# ProPrj_51__2025-03-03.net
KiCad netlist of a schematic drawn in EasyEDA Pro
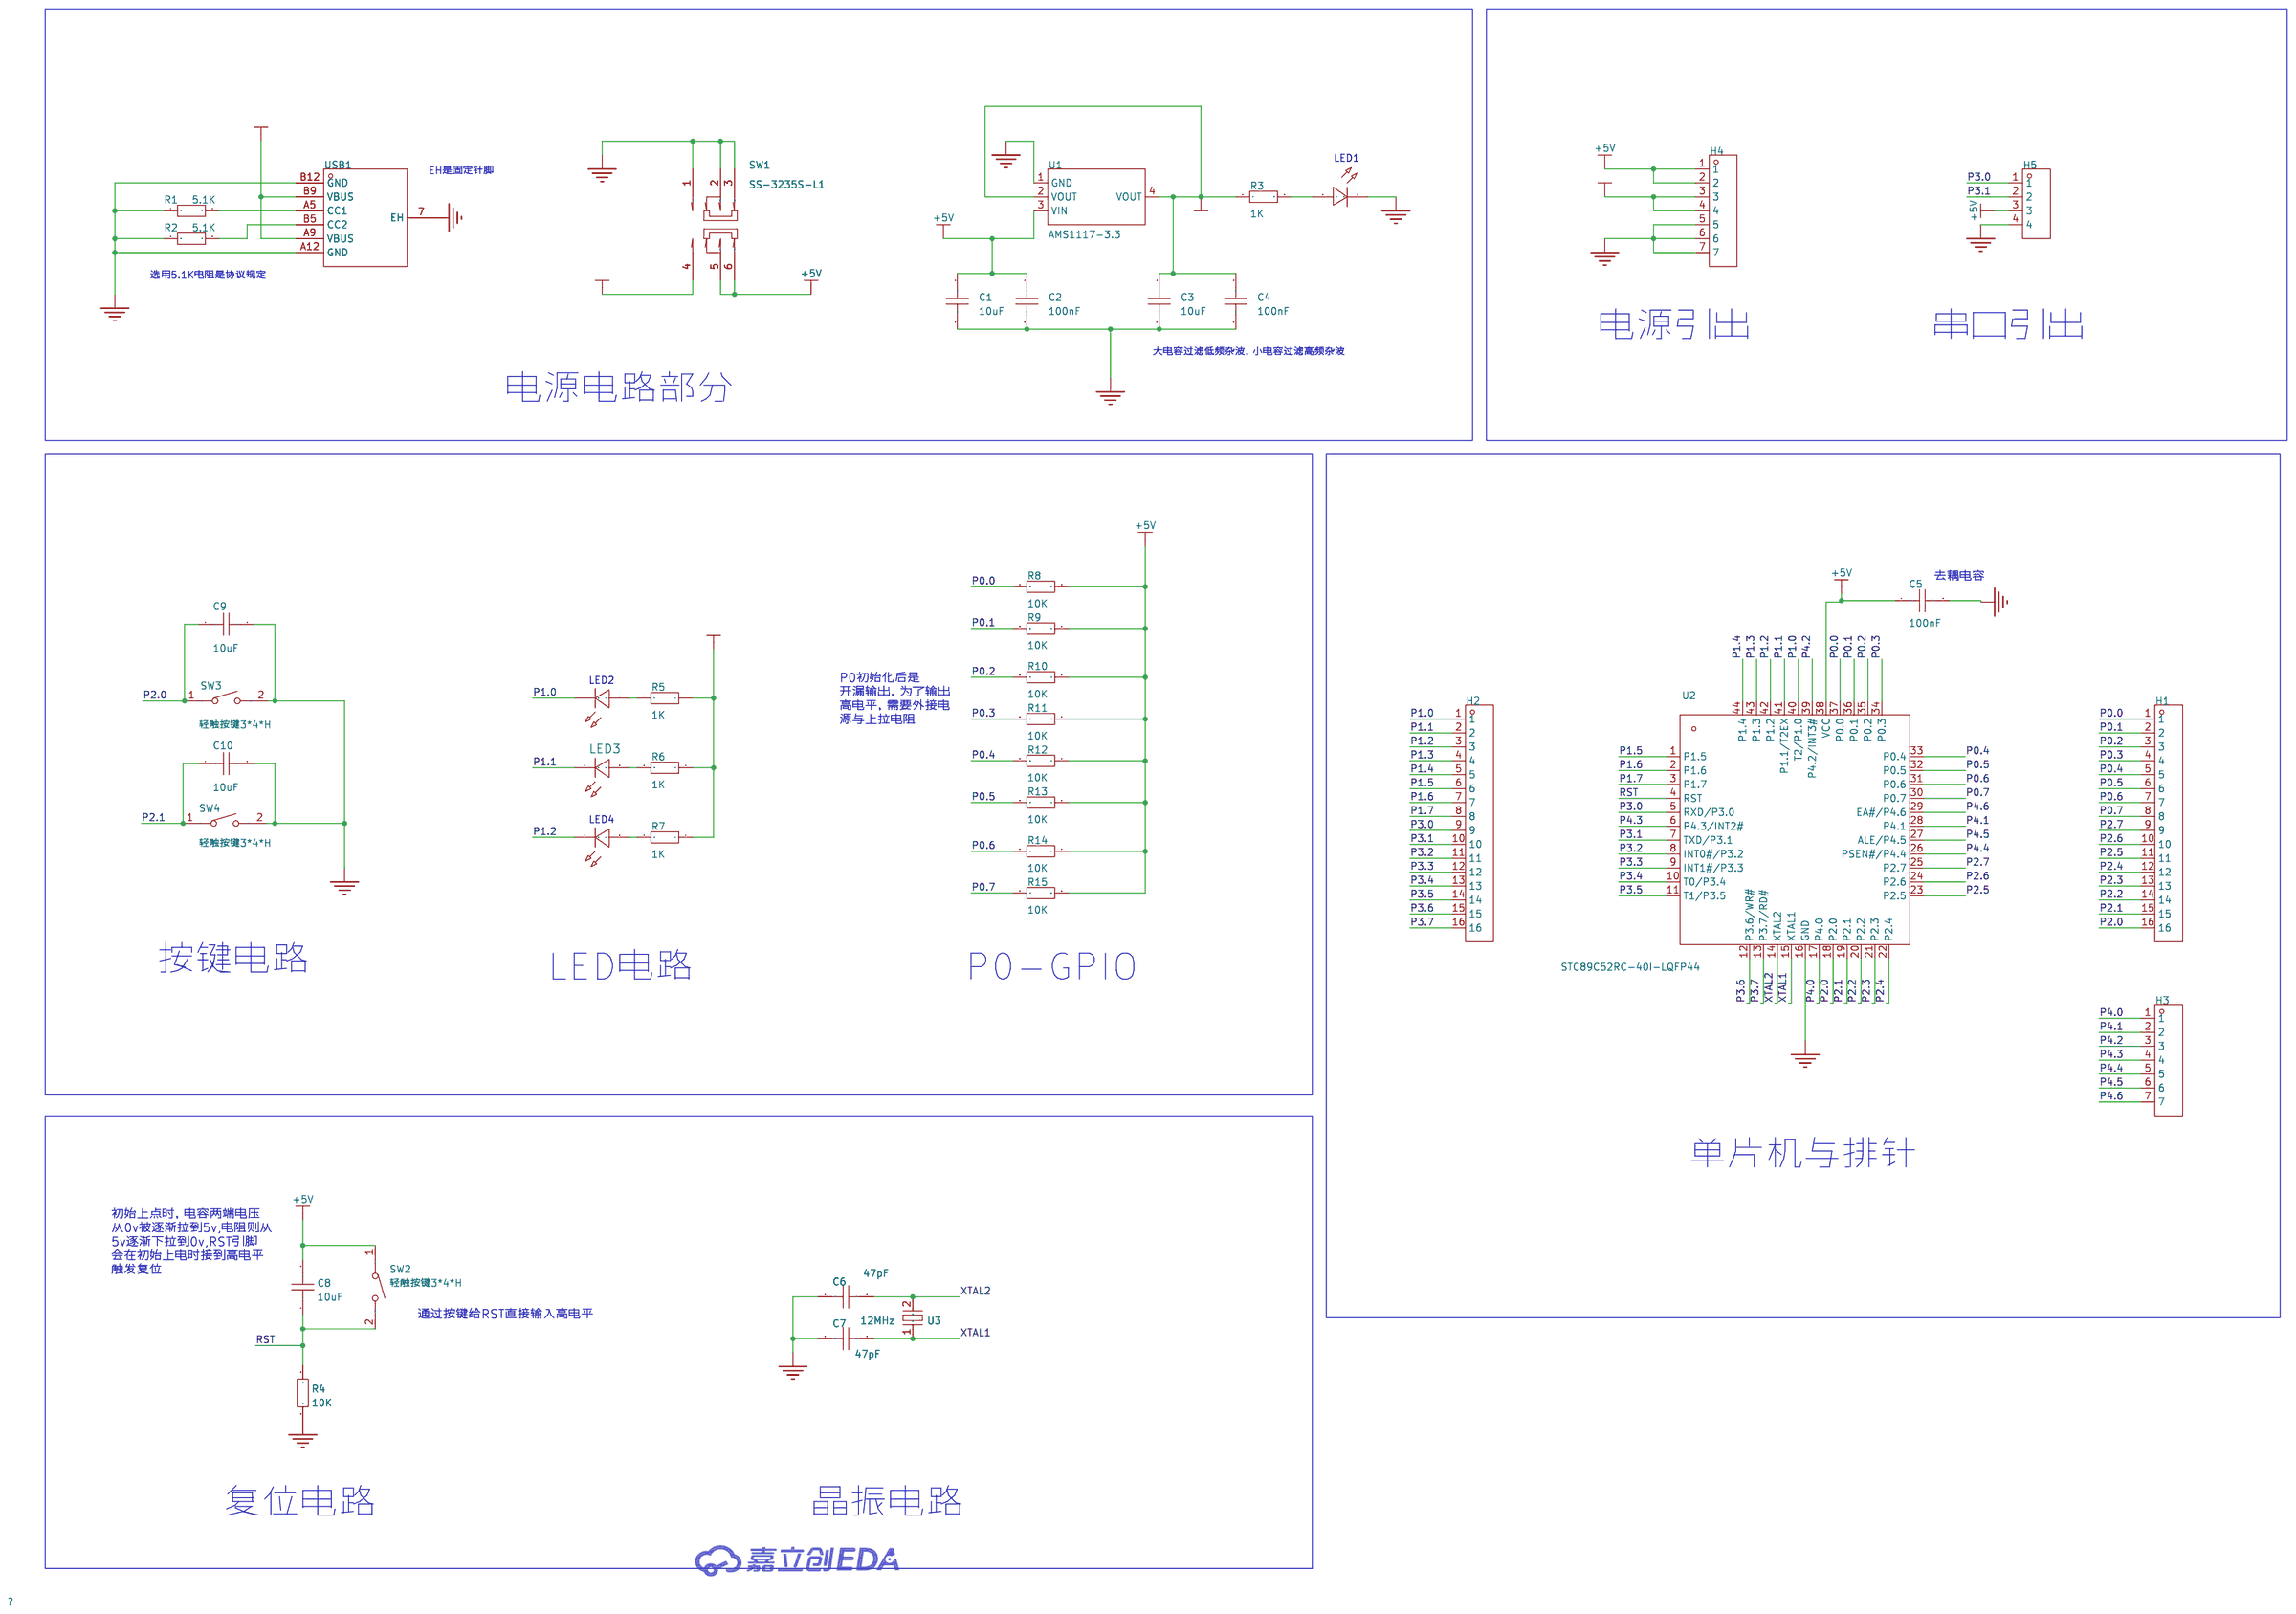
[diagram p0: schematic sheet]

(export (version "E")
  (design (tool "Eeschema 10.0.6"))
  (components
    (comp (ref "C1")
      (value "10uF")
      (footprint "easyedapro:C0805")
      (libsource (lib "easyedapro") (part "CapAcitance"))
    )
    (comp (ref "C2")
      (value "100nF")
      (footprint "easyedapro:C0805")
      (libsource (lib "easyedapro") (part "CapAcitance"))
    )
    (comp (ref "C3")
      (value "10uF")
      (footprint "easyedapro:C0805")
      (libsource (lib "easyedapro") (part "CapAcitance"))
    )
    (comp (ref "C4")
      (value "100nF")
      (footprint "easyedapro:C0805")
      (libsource (lib "easyedapro") (part "CapAcitance"))
    )
    (comp (ref "C5")
      (value "100nF")
      (footprint "easyedapro:C0805")
      (libsource (lib "easyedapro") (part "CapAcitance"))
    )
    (comp (ref "C6")
      (value "47pF")
      (footprint "easyedapro:C0805")
      (libsource (lib "easyedapro") (part "CapAcitance"))
    )
    (comp (ref "C7")
      (value "47pF")
      (footprint "easyedapro:C0805")
      (libsource (lib "easyedapro") (part "CapAcitance"))
    )
    (comp (ref "C8")
      (value "10uF")
      (footprint "easyedapro:C0805")
      (libsource (lib "easyedapro") (part "CapAcitance"))
    )
    (comp (ref "C9")
      (value "10uF")
      (footprint "easyedapro:C0805")
      (libsource (lib "easyedapro") (part "CapAcitance"))
    )
    (comp (ref "C10")
      (value "10uF")
      (footprint "easyedapro:C0805")
      (libsource (lib "easyedapro") (part "CapAcitance"))
    )
    (comp (ref "H1")
      (value "~")
      (footprint "easyedapro:HDR-TH_16P-P2.54-V-M")
      (libsource (lib "easyedapro") (part "HDR_2.54-1x16P"))
    )
    (comp (ref "H2")
      (value "~")
      (footprint "easyedapro:HDR-TH_16P-P2.54-V-M")
      (libsource (lib "easyedapro") (part "HDR_2.54-1x16P"))
    )
    (comp (ref "H3")
      (value "~")
      (footprint "easyedapro:HDR-TH_7P-P2.54-V-M")
      (libsource (lib "easyedapro") (part "PZ254V-11-07P"))
    )
    (comp (ref "H4")
      (value "~")
      (footprint "easyedapro:HDR-TH_7P-P2.54-V-M")
      (libsource (lib "easyedapro") (part "PZ254V-11-07P"))
    )
    (comp (ref "H5")
      (value "~")
      (footprint "easyedapro:HDR-TH_4P-P2.54-V-M")
      (libsource (lib "easyedapro") (part "PZ254V-11-04P"))
    )
    (comp (ref "LED1")
      (value "~")
      (footprint "easyedapro:LED_0805")
      (libsource (lib "easyedapro") (part "LED_G"))
    )
    (comp (ref "LED2")
      (value "~")
      (footprint "easyedapro:LED_0805")
      (libsource (lib "easyedapro") (part "LED_G"))
    )
    (comp (ref "LED3")
      (value "~")
      (footprint "easyedapro:LED_0805")
      (libsource (lib "easyedapro") (part "LED_R"))
    )
    (comp (ref "LED4")
      (value "~")
      (footprint "easyedapro:LED_0805")
      (libsource (lib "easyedapro") (part "LED_B"))
    )
    (comp (ref "R1") (value "5.1K") (footprint "easyedapro:R0805") (libsource (lib "easyedapro") (part "电阻")))
    (comp (ref "R2") (value "5.1K") (footprint "easyedapro:R0805") (libsource (lib "easyedapro") (part "电阻")))
    (comp (ref "R3") (value "1K") (footprint "easyedapro:R0805") (libsource (lib "easyedapro") (part "电阻")))
    (comp (ref "R4") (value "10K") (footprint "easyedapro:R0805") (libsource (lib "easyedapro") (part "电阻")))
    (comp (ref "R5") (value "1K") (footprint "easyedapro:R0805") (libsource (lib "easyedapro") (part "电阻")))
    (comp (ref "R6") (value "1K") (footprint "easyedapro:R0805") (libsource (lib "easyedapro") (part "电阻")))
    (comp (ref "R7") (value "1K") (footprint "easyedapro:R0805") (libsource (lib "easyedapro") (part "电阻")))
    (comp (ref "R8") (value "10K") (footprint "easyedapro:R0805") (libsource (lib "easyedapro") (part "电阻")))
    (comp (ref "R9") (value "10K") (footprint "easyedapro:R0805") (libsource (lib "easyedapro") (part "电阻")))
    (comp (ref "R10") (value "10K") (footprint "easyedapro:R0805") (libsource (lib "easyedapro") (part "电阻")))
    (comp (ref "R11") (value "10K") (footprint "easyedapro:R0805") (libsource (lib "easyedapro") (part "电阻")))
    (comp (ref "R12") (value "10K") (footprint "easyedapro:R0805") (libsource (lib "easyedapro") (part "电阻")))
    (comp (ref "R13") (value "10K") (footprint "easyedapro:R0805") (libsource (lib "easyedapro") (part "电阻")))
    (comp (ref "R14") (value "10K") (footprint "easyedapro:R0805") (libsource (lib "easyedapro") (part "电阻")))
    (comp (ref "R15") (value "10K") (footprint "easyedapro:R0805") (libsource (lib "easyedapro") (part "电阻")))
    (comp (ref "SW1")
      (value "SS-3235S-L1")
      (footprint "easyedapro:SW-SMD_SS-3235S-LX")
      (description "电路结构:双刀双掷;安装方式:卧贴;开关颜色:黑色;额定电流(DC):50mA;额定电压(DC):12V;额定电流(AC):50mA;额定电压(AC):12V;机械寿命:1万次;")
      (fields (field (name "Manufacturer") "XKB Connectivity(中国星坤)"))
      (libsource (lib "easyedapro") (part "SS-3235S-L1"))
    )
    (comp (ref "SW2")
      (value "轻触按键3*4*H")
      (footprint "easyedapro:SW-SMD_L4.0-W2.9-LS5.0")
      (libsource (lib "easyedapro") (part "轻触按键3*4*H"))
    )
    (comp (ref "SW3")
      (value "轻触按键3*4*H")
      (footprint "easyedapro:SW-SMD_L4.0-W2.9-LS5.0")
      (libsource (lib "easyedapro") (part "轻触按键3*4*H"))
    )
    (comp (ref "SW4")
      (value "轻触按键3*4*H")
      (footprint "easyedapro:SW-SMD_L4.0-W2.9-LS5.0")
      (libsource (lib "easyedapro") (part "轻触按键3*4*H"))
    )
    (comp (ref "U1")
      (value "AMS1117-3.3")
      (footprint "easyedapro:SOT-223-3_L6.5-W3.4-P2.30-LS7.0-BR")
      (description "输出类型:固定;工作电压:-;输出电压:3.3V;输出电流:1A;电源纹波抑制比(PSRR):72dB@(120Hz);输出极性:正极;")
      (fields (field (name "Manufacturer") "AMS"))
      (libsource (lib "easyedapro") (part "AMS1117-3.3"))
    )
    (comp (ref "U2")
      (value "STC89C52RC-40I-LQFP44")
      (footprint "easyedapro:LQFP-44_L10.0-W10.0-P0.80-LS12.0-BL")
      (description "CPU内核:51系列;应用领域:-;")
      (fields (field (name "Manufacturer") "STC"))
      (libsource (lib "easyedapro") (part "STC89C52RC-40I_C8707"))
    )
    (comp (ref "U3")
      (value "12MHz")
      (footprint "easyedapro:CRYSTAL-SMD_L11.4-W4.7-LS12.7")
      (description "频率:12MHz;常温频差:±30ppm;外接负载电容:18pF;频率稳定度(全温):±35ppm;")
      (fields
        (field (name "Manufacturer Part") "ABLS-12.000MHZ-B4H-T")
        (field (name "Manufacturer") "ABRACON")
      )
      (libsource (lib "easyedapro") (part "ABLS-12.000MHZ-B4H-T"))
    )
    (comp (ref "USB1")
      (value "TYPE-C-6P-DIP2X2")
      (footprint "easyedapro:TYPE-C-SMD_TYPE-C-6P")
      (libsource (lib "easyedapro") (part "TYPE-C-6P-DIP2X2"))
    )
  )
  (nets
    (net (code "1") (name "+3.3V") (class "Default")
      (node (ref "C3") (pin "1") (pinfunction "1_1") (pintype "input"))
      (node (ref "C4") (pin "1") (pinfunction "1_1") (pintype "input"))
      (node (ref "H4") (pin "3") (pinfunction "3_3") (pintype "unspecified"))
      (node (ref "H4") (pin "4") (pinfunction "4_4") (pintype "unspecified"))
      (node (ref "R3") (pin "1") (pinfunction "1_1") (pintype "input"))
      (node (ref "R5") (pin "1") (pinfunction "1_1") (pintype "input"))
      (node (ref "R6") (pin "1") (pinfunction "1_1") (pintype "input"))
      (node (ref "R7") (pin "1") (pinfunction "1_1") (pintype "input"))
      (node (ref "U1") (pin "2") (pinfunction "VOUT_2") (pintype "unspecified"))
      (node (ref "U1") (pin "4") (pinfunction "VOUT_4") (pintype "unspecified"))
    )
    (net (code "2") (name "+5V") (class "Default")
      (node (ref "C1") (pin "1") (pinfunction "1_1") (pintype "input"))
      (node (ref "C2") (pin "1") (pinfunction "1_1") (pintype "input"))
      (node (ref "C5") (pin "1") (pinfunction "1_1") (pintype "input"))
      (node (ref "C8") (pin "2") (pinfunction "2_2") (pintype "input"))
      (node (ref "H4") (pin "1") (pinfunction "1_1") (pintype "unspecified"))
      (node (ref "H4") (pin "2") (pinfunction "2_2") (pintype "unspecified"))
      (node (ref "H5") (pin "3") (pinfunction "3_3") (pintype "unspecified"))
      (node (ref "R10") (pin "1") (pinfunction "1_1") (pintype "input"))
      (node (ref "R11") (pin "1") (pinfunction "1_1") (pintype "input"))
      (node (ref "R12") (pin "1") (pinfunction "1_1") (pintype "input"))
      (node (ref "R13") (pin "1") (pinfunction "1_1") (pintype "input"))
      (node (ref "R14") (pin "1") (pinfunction "1_1") (pintype "input"))
      (node (ref "R15") (pin "1") (pinfunction "1_1") (pintype "input"))
      (node (ref "R8") (pin "1") (pinfunction "1_1") (pintype "input"))
      (node (ref "R9") (pin "1") (pinfunction "1_1") (pintype "input"))
      (node (ref "SW1") (pin "5") (pinfunction "5_5") (pintype "unspecified"))
      (node (ref "SW1") (pin "6") (pinfunction "6_6") (pintype "unspecified"))
      (node (ref "SW2") (pin "1") (pinfunction "1_1") (pintype "unspecified"))
      (node (ref "U1") (pin "3") (pinfunction "VIN_3") (pintype "unspecified"))
      (node (ref "U2") (pin "38") (pinfunction "VCC_38") (pintype "unspecified"))
    )
    (net (code "3") (name "/P0.0") (class "Default")
      (node (ref "H1") (pin "1") (pinfunction "1_1") (pintype "input"))
      (node (ref "R8") (pin "2") (pinfunction "2_2") (pintype "input"))
      (node (ref "U2") (pin "37") (pinfunction "P0.0_37") (pintype "unspecified"))
    )
    (net (code "4") (name "/P0.1") (class "Default")
      (node (ref "H1") (pin "2") (pinfunction "2_2") (pintype "input"))
      (node (ref "R9") (pin "2") (pinfunction "2_2") (pintype "input"))
      (node (ref "U2") (pin "36") (pinfunction "P0.1_36") (pintype "unspecified"))
    )
    (net (code "5") (name "/P0.2") (class "Default")
      (node (ref "H1") (pin "3") (pinfunction "3_3") (pintype "input"))
      (node (ref "R10") (pin "2") (pinfunction "2_2") (pintype "input"))
      (node (ref "U2") (pin "35") (pinfunction "P0.2_35") (pintype "unspecified"))
    )
    (net (code "6") (name "/P0.3") (class "Default")
      (node (ref "H1") (pin "4") (pinfunction "4_4") (pintype "input"))
      (node (ref "R11") (pin "2") (pinfunction "2_2") (pintype "input"))
      (node (ref "U2") (pin "34") (pinfunction "P0.3_34") (pintype "unspecified"))
    )
    (net (code "7") (name "/P0.4") (class "Default")
      (node (ref "H1") (pin "5") (pinfunction "5_5") (pintype "input"))
      (node (ref "R12") (pin "2") (pinfunction "2_2") (pintype "input"))
      (node (ref "U2") (pin "33") (pinfunction "P0.4_33") (pintype "unspecified"))
    )
    (net (code "8") (name "/P0.5") (class "Default")
      (node (ref "H1") (pin "6") (pinfunction "6_6") (pintype "input"))
      (node (ref "R13") (pin "2") (pinfunction "2_2") (pintype "input"))
      (node (ref "U2") (pin "32") (pinfunction "P0.5_32") (pintype "unspecified"))
    )
    (net (code "9") (name "/P0.6") (class "Default")
      (node (ref "H1") (pin "7") (pinfunction "7_7") (pintype "input"))
      (node (ref "R14") (pin "2") (pinfunction "2_2") (pintype "input"))
      (node (ref "U2") (pin "31") (pinfunction "P0.6_31") (pintype "unspecified"))
    )
    (net (code "10") (name "/P0.7") (class "Default")
      (node (ref "H1") (pin "8") (pinfunction "8_8") (pintype "input"))
      (node (ref "R15") (pin "2") (pinfunction "2_2") (pintype "input"))
      (node (ref "U2") (pin "30") (pinfunction "P0.7_30") (pintype "unspecified"))
    )
    (net (code "11") (name "/P1.0") (class "Default")
      (node (ref "H2") (pin "1") (pinfunction "1_1") (pintype "input"))
      (node (ref "LED2") (pin "1") (pinfunction "C_1") (pintype "input"))
      (node (ref "U2") (pin "40") (pinfunction "T2/P1.0_40") (pintype "unspecified"))
    )
    (net (code "12") (name "/P1.1") (class "Default")
      (node (ref "H2") (pin "2") (pinfunction "2_2") (pintype "input"))
      (node (ref "LED3") (pin "1") (pinfunction "C_1") (pintype "input"))
      (node (ref "U2") (pin "41") (pinfunction "P1.1/T2EX_41") (pintype "unspecified"))
    )
    (net (code "13") (name "/P1.2") (class "Default")
      (node (ref "H2") (pin "3") (pinfunction "3_3") (pintype "input"))
      (node (ref "LED4") (pin "1") (pinfunction "C_1") (pintype "input"))
      (node (ref "U2") (pin "42") (pinfunction "P1.2_42") (pintype "unspecified"))
    )
    (net (code "14") (name "/P1.3") (class "Default")
      (node (ref "H2") (pin "4") (pinfunction "4_4") (pintype "input"))
      (node (ref "U2") (pin "43") (pinfunction "P1.3_43") (pintype "unspecified"))
    )
    (net (code "15") (name "/P1.4") (class "Default")
      (node (ref "H2") (pin "5") (pinfunction "5_5") (pintype "input"))
      (node (ref "U2") (pin "44") (pinfunction "P1.4_44") (pintype "unspecified"))
    )
    (net (code "16") (name "/P1.5") (class "Default")
      (node (ref "H2") (pin "6") (pinfunction "6_6") (pintype "input"))
      (node (ref "U2") (pin "1") (pinfunction "P1.5_1") (pintype "unspecified"))
    )
    (net (code "17") (name "/P1.6") (class "Default")
      (node (ref "H2") (pin "7") (pinfunction "7_7") (pintype "input"))
      (node (ref "U2") (pin "2") (pinfunction "P1.6_2") (pintype "unspecified"))
    )
    (net (code "18") (name "/P1.7") (class "Default")
      (node (ref "H2") (pin "8") (pinfunction "8_8") (pintype "input"))
      (node (ref "U2") (pin "3") (pinfunction "P1.7_3") (pintype "unspecified"))
    )
    (net (code "19") (name "/P2.0") (class "Default")
      (node (ref "C9") (pin "1") (pinfunction "1_1") (pintype "input"))
      (node (ref "H1") (pin "16") (pinfunction "16_16") (pintype "input"))
      (node (ref "SW3") (pin "1") (pinfunction "1_1") (pintype "unspecified"))
      (node (ref "U2") (pin "18") (pinfunction "P2.0_18") (pintype "unspecified"))
    )
    (net (code "20") (name "/P2.1") (class "Default")
      (node (ref "C10") (pin "1") (pinfunction "1_1") (pintype "input"))
      (node (ref "H1") (pin "15") (pinfunction "15_15") (pintype "input"))
      (node (ref "SW4") (pin "1") (pinfunction "1_1") (pintype "unspecified"))
      (node (ref "U2") (pin "19") (pinfunction "P2.1_19") (pintype "unspecified"))
    )
    (net (code "21") (name "/P2.2") (class "Default")
      (node (ref "H1") (pin "14") (pinfunction "14_14") (pintype "input"))
      (node (ref "U2") (pin "20") (pinfunction "P2.2_20") (pintype "unspecified"))
    )
    (net (code "22") (name "/P2.3") (class "Default")
      (node (ref "H1") (pin "13") (pinfunction "13_13") (pintype "input"))
      (node (ref "U2") (pin "21") (pinfunction "P2.3_21") (pintype "unspecified"))
    )
    (net (code "23") (name "/P2.4") (class "Default")
      (node (ref "H1") (pin "12") (pinfunction "12_12") (pintype "input"))
      (node (ref "U2") (pin "22") (pinfunction "P2.4_22") (pintype "unspecified"))
    )
    (net (code "24") (name "/P2.5") (class "Default")
      (node (ref "H1") (pin "11") (pinfunction "11_11") (pintype "input"))
      (node (ref "U2") (pin "23") (pinfunction "P2.5_23") (pintype "unspecified"))
    )
    (net (code "25") (name "/P2.6") (class "Default")
      (node (ref "H1") (pin "10") (pinfunction "10_10") (pintype "input"))
      (node (ref "U2") (pin "24") (pinfunction "P2.6_24") (pintype "unspecified"))
    )
    (net (code "26") (name "/P2.7") (class "Default")
      (node (ref "H1") (pin "9") (pinfunction "9_9") (pintype "input"))
      (node (ref "U2") (pin "25") (pinfunction "P2.7_25") (pintype "unspecified"))
    )
    (net (code "27") (name "/P3.0") (class "Default")
      (node (ref "H2") (pin "9") (pinfunction "9_9") (pintype "input"))
      (node (ref "H5") (pin "1") (pinfunction "1_1") (pintype "unspecified"))
      (node (ref "U2") (pin "5") (pinfunction "RXD/P3.0_5") (pintype "unspecified"))
    )
    (net (code "28") (name "/P3.1") (class "Default")
      (node (ref "H2") (pin "10") (pinfunction "10_10") (pintype "input"))
      (node (ref "H5") (pin "2") (pinfunction "2_2") (pintype "unspecified"))
      (node (ref "U2") (pin "7") (pinfunction "TXD/P3.1_7") (pintype "unspecified"))
    )
    (net (code "29") (name "/P3.2") (class "Default")
      (node (ref "H2") (pin "11") (pinfunction "11_11") (pintype "input"))
      (node (ref "U2") (pin "8") (pinfunction "INT0#/P3.2_8") (pintype "unspecified"))
    )
    (net (code "30") (name "/P3.3") (class "Default")
      (node (ref "H2") (pin "12") (pinfunction "12_12") (pintype "input"))
      (node (ref "U2") (pin "9") (pinfunction "INT1#/P3.3_9") (pintype "unspecified"))
    )
    (net (code "31") (name "/P3.4") (class "Default")
      (node (ref "H2") (pin "13") (pinfunction "13_13") (pintype "input"))
      (node (ref "U2") (pin "10") (pinfunction "T0/P3.4_10") (pintype "unspecified"))
    )
    (net (code "32") (name "/P3.5") (class "Default")
      (node (ref "H2") (pin "14") (pinfunction "14_14") (pintype "input"))
      (node (ref "U2") (pin "11") (pinfunction "T1/P3.5_11") (pintype "unspecified"))
    )
    (net (code "33") (name "/P3.6") (class "Default")
      (node (ref "H2") (pin "15") (pinfunction "15_15") (pintype "input"))
      (node (ref "U2") (pin "12") (pinfunction "P3.6/WR#_12") (pintype "unspecified"))
    )
    (net (code "34") (name "/P3.7") (class "Default")
      (node (ref "H2") (pin "16") (pinfunction "16_16") (pintype "input"))
      (node (ref "U2") (pin "13") (pinfunction "P3.7/RD#_13") (pintype "unspecified"))
    )
    (net (code "35") (name "/P4.0") (class "Default")
      (node (ref "H3") (pin "1") (pinfunction "1_1") (pintype "unspecified"))
      (node (ref "U2") (pin "17") (pinfunction "P4.0_17") (pintype "unspecified"))
    )
    (net (code "36") (name "/P4.1") (class "Default")
      (node (ref "H3") (pin "2") (pinfunction "2_2") (pintype "unspecified"))
      (node (ref "U2") (pin "28") (pinfunction "P4.1_28") (pintype "unspecified"))
    )
    (net (code "37") (name "/P4.2") (class "Default")
      (node (ref "H3") (pin "3") (pinfunction "3_3") (pintype "unspecified"))
      (node (ref "U2") (pin "39") (pinfunction "P4.2/INT3#_39") (pintype "unspecified"))
    )
    (net (code "38") (name "/P4.3") (class "Default")
      (node (ref "H3") (pin "4") (pinfunction "4_4") (pintype "unspecified"))
      (node (ref "U2") (pin "6") (pinfunction "P4.3/INT2#_6") (pintype "unspecified"))
    )
    (net (code "39") (name "/P4.4") (class "Default")
      (node (ref "H3") (pin "5") (pinfunction "5_5") (pintype "unspecified"))
      (node (ref "U2") (pin "26") (pinfunction "PSEN#/P4.4_26") (pintype "unspecified"))
    )
    (net (code "40") (name "/P4.5") (class "Default")
      (node (ref "H3") (pin "6") (pinfunction "6_6") (pintype "unspecified"))
      (node (ref "U2") (pin "27") (pinfunction "ALE/P4.5_27") (pintype "unspecified"))
    )
    (net (code "41") (name "/P4.6") (class "Default")
      (node (ref "H3") (pin "7") (pinfunction "7_7") (pintype "unspecified"))
      (node (ref "U2") (pin "29") (pinfunction "EA#/P4.6_29") (pintype "unspecified"))
    )
    (net (code "42") (name "/RST") (class "Default")
      (node (ref "C8") (pin "1") (pinfunction "1_1") (pintype "input"))
      (node (ref "R4") (pin "2") (pinfunction "2_2") (pintype "input"))
      (node (ref "SW2") (pin "2") (pinfunction "2_2") (pintype "unspecified"))
      (node (ref "U2") (pin "4") (pinfunction "RST_4") (pintype "unspecified"))
    )
    (net (code "43") (name "/XTAL1") (class "Default")
      (node (ref "C7") (pin "2") (pinfunction "2_2") (pintype "input"))
      (node (ref "U2") (pin "15") (pinfunction "XTAL1_15") (pintype "unspecified"))
      (node (ref "U3") (pin "1") (pinfunction "1_1") (pintype "input"))
    )
    (net (code "44") (name "/XTAL2") (class "Default")
      (node (ref "C6") (pin "2") (pinfunction "2_2") (pintype "input"))
      (node (ref "U2") (pin "14") (pinfunction "XTAL2_14") (pintype "unspecified"))
      (node (ref "U3") (pin "2") (pinfunction "GND_2") (pintype "input"))
    )
    (net (code "45") (name "GND") (class "Default")
      (node (ref "C1") (pin "2") (pinfunction "2_2") (pintype "input"))
      (node (ref "C10") (pin "2") (pinfunction "2_2") (pintype "input"))
      (node (ref "C2") (pin "2") (pinfunction "2_2") (pintype "input"))
      (node (ref "C3") (pin "2") (pinfunction "2_2") (pintype "input"))
      (node (ref "C4") (pin "2") (pinfunction "2_2") (pintype "input"))
      (node (ref "C5") (pin "2") (pinfunction "2_2") (pintype "input"))
      (node (ref "C6") (pin "1") (pinfunction "1_1") (pintype "input"))
      (node (ref "C7") (pin "1") (pinfunction "1_1") (pintype "input"))
      (node (ref "C9") (pin "2") (pinfunction "2_2") (pintype "input"))
      (node (ref "H4") (pin "5") (pinfunction "5_5") (pintype "unspecified"))
      (node (ref "H4") (pin "6") (pinfunction "6_6") (pintype "unspecified"))
      (node (ref "H4") (pin "7") (pinfunction "7_7") (pintype "unspecified"))
      (node (ref "H5") (pin "4") (pinfunction "4_4") (pintype "unspecified"))
      (node (ref "LED1") (pin "1") (pinfunction "C_1") (pintype "input"))
      (node (ref "R1") (pin "1") (pinfunction "1_1") (pintype "input"))
      (node (ref "R2") (pin "1") (pinfunction "1_1") (pintype "input"))
      (node (ref "R4") (pin "1") (pinfunction "1_1") (pintype "input"))
      (node (ref "SW1") (pin "1") (pinfunction "1_1") (pintype "unspecified"))
      (node (ref "SW1") (pin "2") (pinfunction "2_2") (pintype "unspecified"))
      (node (ref "SW1") (pin "3") (pinfunction "3_3") (pintype "unspecified"))
      (node (ref "SW3") (pin "2") (pinfunction "2_2") (pintype "unspecified"))
      (node (ref "SW4") (pin "2") (pinfunction "2_2") (pintype "unspecified"))
      (node (ref "U1") (pin "1") (pinfunction "GND_1") (pintype "unspecified"))
      (node (ref "U2") (pin "16") (pinfunction "GND_16") (pintype "unspecified"))
      (node (ref "USB1") (pin "7") (pinfunction "EH_7") (pintype "unspecified"))
      (node (ref "USB1") (pin "A12") (pinfunction "GND_A12") (pintype "unspecified"))
      (node (ref "USB1") (pin "B12") (pinfunction "GND_B12") (pintype "unspecified"))
    )
    (net (code "46") (name "Net-(LED1-A)") (class "Default")
      (node (ref "LED1") (pin "2") (pinfunction "A_2") (pintype "input"))
      (node (ref "R3") (pin "2") (pinfunction "2_2") (pintype "input"))
    )
    (net (code "47") (name "Net-(LED2-A)") (class "Default")
      (node (ref "LED2") (pin "2") (pinfunction "A_2") (pintype "input"))
      (node (ref "R5") (pin "2") (pinfunction "2_2") (pintype "input"))
    )
    (net (code "48") (name "Net-(LED3-A)") (class "Default")
      (node (ref "LED3") (pin "2") (pinfunction "A_2") (pintype "input"))
      (node (ref "R6") (pin "2") (pinfunction "2_2") (pintype "input"))
    )
    (net (code "49") (name "Net-(LED4-A)") (class "Default")
      (node (ref "LED4") (pin "2") (pinfunction "A_2") (pintype "input"))
      (node (ref "R7") (pin "2") (pinfunction "2_2") (pintype "input"))
    )
    (net (code "50") (name "Net-(USB1-CC1)") (class "Default")
      (node (ref "R1") (pin "2") (pinfunction "2_2") (pintype "input"))
      (node (ref "USB1") (pin "A5") (pinfunction "CC1_A5") (pintype "unspecified"))
    )
    (net (code "51") (name "Net-(USB1-CC2)") (class "Default")
      (node (ref "R2") (pin "2") (pinfunction "2_2") (pintype "input"))
      (node (ref "USB1") (pin "B5") (pinfunction "CC2_B5") (pintype "unspecified"))
    )
    (net (code "52") (name "VCC+5V") (class "Default")
      (node (ref "SW1") (pin "4") (pinfunction "4_4") (pintype "unspecified"))
      (node (ref "USB1") (pin "A9") (pinfunction "VBUS_A9") (pintype "unspecified"))
      (node (ref "USB1") (pin "B9") (pinfunction "VBUS_B9") (pintype "unspecified"))
    )
  )
)
